# design.net
KiCad netlist of a schematic drawn in EasyEDA Pro
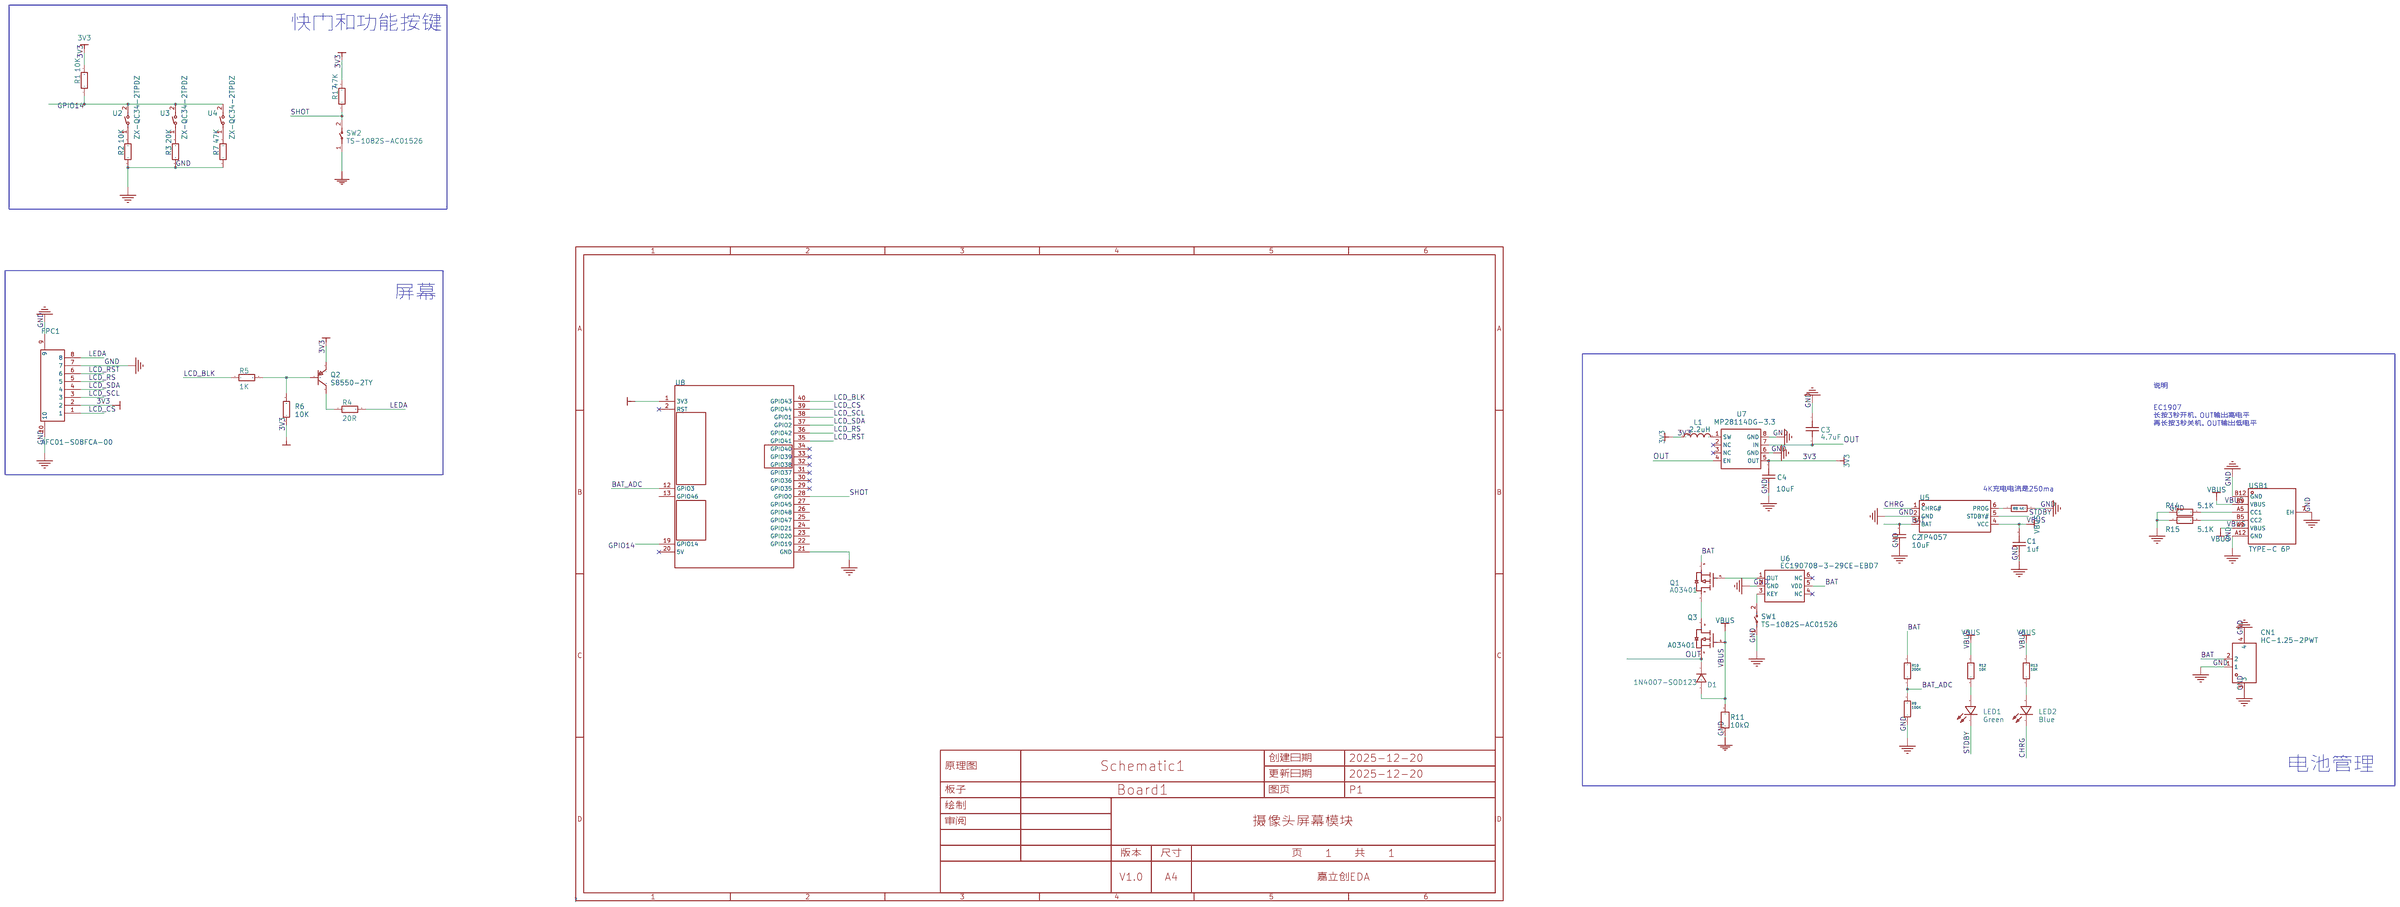
[diagram p0: schematic sheet]

(export (version "E")
  (design (tool "Eeschema 10.0.6"))
  (components
    (comp (ref "C1")
      (value "1uf")
      (footprint "easyedapro:C0603")
      (libsource (lib "easyedapro") (part "Capacitance"))
    )
    (comp (ref "C2")
      (value "10uF")
      (footprint "easyedapro:C0402")
      (description "容值:10uF;精度:±20%;额定电压:6.3V;温度系数:X5R;")
      (fields
        (field (name "Manufacturer Part") "CL05A106MQ5NUNC")
        (field (name "Manufacturer") "SAMSUNG(三星)")
      )
      (libsource (lib "easyedapro") (part "CL05A106MQ5NUNC"))
    )
    (comp (ref "C3")
      (value "4.7uF")
      (footprint "easyedapro:C0603_1")
      (fields
        (field (name "Manufacturer Part") "1uF")
        (field (name "Manufacturer") "SAMSUNG(三星)")
        (field (name "Contributor") "LCSC")
      )
      (libsource (lib "easyedapro") (part "4.7uF"))
    )
    (comp (ref "C4")
      (value "10uF")
      (footprint "easyedapro:C0603_1")
      (fields (field (name "Manufacturer") "SAMSUNG(三星)") (field (name "Contributor") "LCSC"))
      (libsource (lib "easyedapro") (part "10uF"))
    )
    (comp (ref "CN1")
      (value "HC-1.25-2PWT")
      (footprint "easyedapro:CONN-SMD_2P-P1.25-HC-1.25-2PWT")
      (fields (field (name "Manufacturer") "HCTL(华灿天禄)"))
      (libsource (lib "easyedapro") (part "HC-1.25-2PWT"))
    )
    (comp (ref "D1")
      (value "1N4007-SOD123")
      (footprint "easyedapro:SOD-123FL_L2.8-W1.8-LS3.7-RD-1")
      (fields (field (name "Contributor") "LCSC"))
      (libsource (lib "easyedapro") (part "1N4007-SOD123"))
    )
    (comp (ref "FPC1")
      (value "AFC01-S08FCA-00")
      (footprint "easyedapro:FPC-SMD_P0.50-8P_FGS-XJ-H2.0")
      (description "锁定特性:翻盖式;触点类型:下接;触点数量:8P;间距:0.5mm;安装方式:卧贴;")
      (fields (field (name "Manufacturer") "JS(钜硕电子)"))
      (libsource (lib "easyedapro") (part "AFC01-S08FCA-00"))
    )
    (comp (ref "L1")
      (value "2.2uH")
      (footprint "easyedapro:IND-SMD_L4.4-W4.0_PHC0420")
      (fields
        (field (name "Manufacturer Part") "APH0420T2R2M")
        (field (name "Manufacturer") "APV(爱普微)")
        (field (name "Contributor") "lcsc")
      )
      (libsource (lib "easyedapro") (part "2.2uH"))
    )
    (comp (ref "LED1")
      (value "Green")
      (footprint "easyedapro:LED0603-RD")
      (fields (field (name "Manufacturer") "国星光电"))
      (libsource (lib "easyedapro") (part "FC-1608YXK-585F08"))
    )
    (comp (ref "LED2")
      (value "Blue")
      (footprint "easyedapro:LED0603-RD")
      (fields (field (name "Manufacturer") "国星光电"))
      (libsource (lib "easyedapro") (part "FC-1608YXK-585F08"))
    )
    (comp (ref "Q1")
      (value "A03401")
      (footprint "easyedapro:A03401")
      (fields (field (name "Contributor") "shanggan"))
      (libsource (lib "easyedapro") (part "A03401"))
    )
    (comp (ref "Q2")
      (value "S8550-2TY")
      (footprint "easyedapro:SOT-23-3_L2.9-W1.3-P0.95-LS2.4-BR")
      (fields (field (name "Manufacturer") "MDD(辰达半导体)"))
      (libsource (lib "easyedapro") (part "S8550-2TY"))
    )
    (comp (ref "Q3")
      (value "A03401")
      (footprint "easyedapro:A03401")
      (fields (field (name "Contributor") "shanggan"))
      (libsource (lib "easyedapro") (part "A03401_1"))
    )
    (comp (ref "R1") (value "10K") (libsource (lib "easyedapro") (part "电阻")))
    (comp (ref "R2") (value "10K") (libsource (lib "easyedapro") (part "电阻")))
    (comp (ref "R3") (value "20K") (libsource (lib "easyedapro") (part "电阻")))
    (comp (ref "R4")
      (value "20R")
      (footprint "easyedapro:R0603")
      (libsource (lib "easyedapro") (part "电阻_1"))
    )
    (comp (ref "R5") (value "1K") (footprint "easyedapro:R0603") (libsource (lib "easyedapro") (part "电阻_1")))
    (comp (ref "R6")
      (value "10K")
      (footprint "easyedapro:R0603")
      (libsource (lib "easyedapro") (part "电阻_1"))
    )
    (comp (ref "R7") (value "47K") (libsource (lib "easyedapro") (part "电阻")))
    (comp (ref "R8") (value "4K") (footprint "easyedapro:R0603") (libsource (lib "easyedapro") (part "电阻_1")))
    (comp (ref "R9")
      (value "100K")
      (footprint "easyedapro:R0603")
      (libsource (lib "easyedapro") (part "电阻_1"))
    )
    (comp (ref "R10")
      (value "200K")
      (footprint "easyedapro:R0603")
      (libsource (lib "easyedapro") (part "电阻_1"))
    )
    (comp (ref "R11")
      (value "10kΩ")
      (footprint "easyedapro:R0603_1")
      (fields
        (field (name "Manufacturer Part") "APC0603T10K0Z")
        (field (name "Manufacturer") "Ohmite")
        (field (name "Contributor") "lcsc")
      )
      (libsource (lib "easyedapro") (part "10kΩ"))
    )
    (comp (ref "R12")
      (value "10K")
      (footprint "easyedapro:R0603")
      (libsource (lib "easyedapro") (part "电阻_1"))
    )
    (comp (ref "R13")
      (value "10K")
      (footprint "easyedapro:R0603")
      (libsource (lib "easyedapro") (part "电阻_1"))
    )
    (comp (ref "R14")
      (value "5.1K")
      (footprint "easyedapro:R0603")
      (libsource (lib "easyedapro") (part "电阻_1"))
    )
    (comp (ref "R15")
      (value "5.1K")
      (footprint "easyedapro:R0603")
      (libsource (lib "easyedapro") (part "电阻_1"))
    )
    (comp (ref "R17") (value "47K") (libsource (lib "easyedapro") (part "电阻")))
    (comp (ref "SW1")
      (value "TS-1082S-AC01526")
      (footprint "easyedapro:SW-SMD_L3.9-W3.6-LS4.8-EH")
      (fields (field (name "Manufacturer") "XUNPU(讯普)"))
      (libsource (lib "easyedapro") (part "TS-1082S-AC01526"))
    )
    (comp (ref "SW2")
      (value "TS-1082S-AC01526")
      (footprint "easyedapro:SW-SMD_L3.9-W3.6-LS4.8-EH")
      (fields (field (name "Manufacturer") "XUNPU(讯普)"))
      (libsource (lib "easyedapro") (part "TS-1082S-AC01526"))
    )
    (comp (ref "U2")
      (value "ZX-QC34-2TPDZ")
      (footprint "easyedapro:KEY-SMD_L3.9-W3.0-LS5.0-EH")
      (fields (field (name "Manufacturer") "Megastar(兆星)"))
      (libsource (lib "easyedapro") (part "ZX-QC34-2TPDZ"))
    )
    (comp (ref "U3")
      (value "ZX-QC34-2TPDZ")
      (footprint "easyedapro:KEY-SMD_L3.9-W3.0-LS5.0-EH")
      (fields (field (name "Manufacturer") "Megastar(兆星)"))
      (libsource (lib "easyedapro") (part "ZX-QC34-2TPDZ"))
    )
    (comp (ref "U4")
      (value "ZX-QC34-2TPDZ")
      (footprint "easyedapro:KEY-SMD_L3.9-W3.0-LS5.0-EH")
      (fields (field (name "Manufacturer") "Megastar(兆星)"))
      (libsource (lib "easyedapro") (part "ZX-QC34-2TPDZ"))
    )
    (comp (ref "U5")
      (value "TP4057")
      (footprint "easyedapro:SOT-23-6_L2.9-W1.6-P0.95-LS2.8-BR")
      (description "工作电压:4V~6.5V;最大充电电流:500mA;电池类型:锂离子;电池节数:1;")
      (fields (field (name "Manufacturer") "UMW(友台半导体)"))
      (libsource (lib "easyedapro") (part "TP4057_C725791"))
    )
    (comp (ref "U6")
      (value "EC190708-3-29CE-EBD7")
      (footprint "easyedapro:SOT-23-6_L2.9-W1.6-P0.95-LS2.9-BL")
      (fields (field (name "Contributor") "lcsc"))
      (libsource (lib "easyedapro") (part "EC190708-3-29CE-EBD7"))
    )
    (comp (ref "U7")
      (value "MP28114DG-3.3")
      (footprint "easyedapro:MP28114DG-3.3")
      (fields (field (name "Contributor") "httppp"))
      (libsource (lib "easyedapro") (part "MP28114DG-3.3"))
    )
    (comp (ref "U8")
      (value "~")
      (footprint "easyedapro:esp32s3_cam模块")
      (libsource (lib "easyedapro") (part "esp32s3_cam模块"))
    )
    (comp (ref "USB1")
      (value "TYPE-C 6P")
      (footprint "easyedapro:TYPE-C-SMD_TYPE-C-6P")
      (description "连接器类型:Type-C;标准:USB 3.1;公母:母;安装方式:卧贴;触点数量:6P;端口数量:1;额定电流 - 电源:5A;工作温度范围:-40℃~+85℃;")
      (fields (field (name "Manufacturer") "SHOU HAN(首韩)"))
      (libsource (lib "easyedapro") (part "TYPE-C 6P"))
    )
  )
  (nets
    (net (code "1") (name "/BAT") (class "Default")
      (node (ref "C2") (pin "2") (pinfunction "2_2") (pintype "input"))
      (node (ref "CN1") (pin "2") (pinfunction "2_2") (pintype "unspecified"))
      (node (ref "Q1") (pin "2") (pinfunction "S_2") (pintype "unspecified"))
      (node (ref "R10") (pin "2") (pinfunction "2_2") (pintype "input"))
      (node (ref "U5") (pin "3") (pinfunction "BAT_3") (pintype "unspecified"))
      (node (ref "U6") (pin "5") (pinfunction "VDD_5") (pintype "unspecified"))
    )
    (net (code "2") (name "/BAT_ADC") (class "Default")
      (node (ref "R10") (pin "1") (pinfunction "1_1") (pintype "input"))
      (node (ref "R9") (pin "2") (pinfunction "2_2") (pintype "input"))
      (node (ref "U8") (pin "12") (pinfunction "GPIO3_12") (pintype "unspecified"))
    )
    (net (code "3") (name "/CHRG") (class "Default")
      (node (ref "LED2") (pin "1") (pinfunction "K_1") (pintype "unspecified"))
      (node (ref "U5") (pin "1") (pinfunction "CHRG#_1") (pintype "unspecified"))
    )
    (net (code "4") (name "/GPIO14") (class "Default")
      (node (ref "R1") (pin "1") (pinfunction "1_1") (pintype "input"))
      (node (ref "U2") (pin "2") (pinfunction "2_2") (pintype "unspecified"))
      (node (ref "U3") (pin "2") (pinfunction "2_2") (pintype "unspecified"))
      (node (ref "U4") (pin "2") (pinfunction "2_2") (pintype "unspecified"))
      (node (ref "U8") (pin "19") (pinfunction "GPIO14_19") (pintype "unspecified"))
    )
    (net (code "5") (name "/LCD_BLK") (class "Default")
      (node (ref "R5") (pin "1") (pinfunction "1_1") (pintype "input"))
      (node (ref "U8") (pin "40") (pinfunction "GPIO43_40") (pintype "unspecified"))
    )
    (net (code "6") (name "/LCD_CS") (class "Default")
      (node (ref "FPC1") (pin "1") (pinfunction "1_1") (pintype "unspecified"))
      (node (ref "U8") (pin "39") (pinfunction "GPIO44_39") (pintype "unspecified"))
    )
    (net (code "7") (name "/LCD_RS") (class "Default")
      (node (ref "FPC1") (pin "5") (pinfunction "5_5") (pintype "unspecified"))
      (node (ref "U8") (pin "36") (pinfunction "GPIO42_36") (pintype "unspecified"))
    )
    (net (code "8") (name "/LCD_RST") (class "Default")
      (node (ref "FPC1") (pin "6") (pinfunction "6_6") (pintype "unspecified"))
      (node (ref "U8") (pin "35") (pinfunction "GPIO41_35") (pintype "unspecified"))
    )
    (net (code "9") (name "/LCD_SCL") (class "Default")
      (node (ref "FPC1") (pin "3") (pinfunction "3_3") (pintype "unspecified"))
      (node (ref "U8") (pin "38") (pinfunction "GPIO1_38") (pintype "unspecified"))
    )
    (net (code "10") (name "/LCD_SDA") (class "Default")
      (node (ref "FPC1") (pin "4") (pinfunction "4_4") (pintype "unspecified"))
      (node (ref "U8") (pin "37") (pinfunction "GPIO2_37") (pintype "unspecified"))
    )
    (net (code "11") (name "/LEDA") (class "Default")
      (node (ref "FPC1") (pin "8") (pinfunction "8_8") (pintype "unspecified"))
      (node (ref "R4") (pin "2") (pinfunction "2_2") (pintype "input"))
    )
    (net (code "12") (name "/OUT") (class "Default")
      (node (ref "C3") (pin "2") (pinfunction "2_2") (pintype "unspecified"))
      (node (ref "D1") (pin "1") (pinfunction "1_1") (pintype "unspecified"))
      (node (ref "Q3") (pin "2") (pinfunction "S_2") (pintype "unspecified"))
      (node (ref "U7") (pin "4") (pinfunction "EN_4") (pintype "unspecified"))
      (node (ref "U7") (pin "7") (pinfunction "IN_7") (pintype "unspecified"))
    )
    (net (code "13") (name "/SHOT") (class "Default")
      (node (ref "R17") (pin "1") (pinfunction "1_1") (pintype "input"))
      (node (ref "SW2") (pin "2") (pinfunction "2_2") (pintype "unspecified"))
      (node (ref "U8") (pin "28") (pinfunction "GPIO0_28") (pintype "unspecified"))
    )
    (net (code "14") (name "/STDBY") (class "Default")
      (node (ref "LED1") (pin "1") (pinfunction "K_1") (pintype "unspecified"))
      (node (ref "U5") (pin "5") (pinfunction "STDBY#_5") (pintype "unspecified"))
    )
    (net (code "15") (name "3V3") (class "Default")
      (node (ref "C4") (pin "1") (pinfunction "1_1") (pintype "unspecified"))
      (node (ref "FPC1") (pin "2") (pinfunction "2_2") (pintype "unspecified"))
      (node (ref "L1") (pin "1") (pinfunction "1_1") (pintype "unspecified"))
      (node (ref "Q2") (pin "2") (pinfunction "E_2") (pintype "unspecified"))
      (node (ref "R1") (pin "2") (pinfunction "2_2") (pintype "input"))
      (node (ref "R17") (pin "2") (pinfunction "2_2") (pintype "input"))
      (node (ref "R6") (pin "1") (pinfunction "1_1") (pintype "input"))
      (node (ref "U7") (pin "5") (pinfunction "OUT_5") (pintype "unspecified"))
      (node (ref "U8") (pin "1") (pinfunction "3V3_1") (pintype "unspecified"))
    )
    (net (code "16") (name "GND") (class "Default")
      (node (ref "C1") (pin "1") (pinfunction "1_1") (pintype "input"))
      (node (ref "C2") (pin "1") (pinfunction "1_1") (pintype "input"))
      (node (ref "C3") (pin "1") (pinfunction "1_1") (pintype "unspecified"))
      (node (ref "C4") (pin "2") (pinfunction "2_2") (pintype "unspecified"))
      (node (ref "CN1") (pin "1") (pinfunction "1_1") (pintype "unspecified"))
      (node (ref "CN1") (pin "3") (pinfunction "3_3") (pintype "unspecified"))
      (node (ref "CN1") (pin "4") (pinfunction "4_4") (pintype "unspecified"))
      (node (ref "FPC1") (pin "10") (pinfunction "10_10") (pintype "unspecified"))
      (node (ref "FPC1") (pin "7") (pinfunction "7_7") (pintype "unspecified"))
      (node (ref "FPC1") (pin "9") (pinfunction "9_9") (pintype "unspecified"))
      (node (ref "R11") (pin "1") (pinfunction "1_1") (pintype "unspecified"))
      (node (ref "R14") (pin "1") (pinfunction "1_1") (pintype "input"))
      (node (ref "R15") (pin "1") (pinfunction "1_1") (pintype "input"))
      (node (ref "R2") (pin "1") (pinfunction "1_1") (pintype "input"))
      (node (ref "R3") (pin "1") (pinfunction "1_1") (pintype "input"))
      (node (ref "R7") (pin "1") (pinfunction "1_1") (pintype "input"))
      (node (ref "R8") (pin "2") (pinfunction "2_2") (pintype "input"))
      (node (ref "R9") (pin "1") (pinfunction "1_1") (pintype "input"))
      (node (ref "SW1") (pin "1") (pinfunction "1_1") (pintype "unspecified"))
      (node (ref "SW2") (pin "1") (pinfunction "1_1") (pintype "unspecified"))
      (node (ref "U5") (pin "2") (pinfunction "GND_2") (pintype "unspecified"))
      (node (ref "U6") (pin "2") (pinfunction "GND_2") (pintype "unspecified"))
      (node (ref "U7") (pin "6") (pinfunction "GND_6") (pintype "unspecified"))
      (node (ref "U7") (pin "8") (pinfunction "GND_8") (pintype "unspecified"))
      (node (ref "U8") (pin "21") (pinfunction "GND_21") (pintype "unspecified"))
      (node (ref "USB1") (pin "7") (pinfunction "EH_7") (pintype "unspecified"))
      (node (ref "USB1") (pin "A12") (pinfunction "GND_A12") (pintype "unspecified"))
      (node (ref "USB1") (pin "B12") (pinfunction "GND_B12") (pintype "unspecified"))
    )
    (net (code "17") (name "Net-(LED1-A)") (class "Default")
      (node (ref "LED1") (pin "2") (pinfunction "A_2") (pintype "unspecified"))
      (node (ref "R12") (pin "2") (pinfunction "2_2") (pintype "input"))
    )
    (net (code "18") (name "Net-(LED2-A)") (class "Default")
      (node (ref "LED2") (pin "2") (pinfunction "A_2") (pintype "unspecified"))
      (node (ref "R13") (pin "1") (pinfunction "1_1") (pintype "input"))
    )
    (net (code "19") (name "Net-(Q1-D)") (class "Default")
      (node (ref "Q1") (pin "3") (pinfunction "D_3") (pintype "unspecified"))
      (node (ref "Q3") (pin "3") (pinfunction "D_3") (pintype "unspecified"))
    )
    (net (code "20") (name "Net-(Q1-G)") (class "Default")
      (node (ref "Q1") (pin "1") (pinfunction "G_1") (pintype "unspecified"))
      (node (ref "U6") (pin "1") (pinfunction "OUT_1") (pintype "unspecified"))
    )
    (net (code "21") (name "Net-(Q2-B)") (class "Default")
      (node (ref "Q2") (pin "1") (pinfunction "B_1") (pintype "unspecified"))
      (node (ref "R5") (pin "2") (pinfunction "2_2") (pintype "input"))
      (node (ref "R6") (pin "2") (pinfunction "2_2") (pintype "input"))
    )
    (net (code "22") (name "Net-(Q2-C)") (class "Default")
      (node (ref "Q2") (pin "3") (pinfunction "C_3") (pintype "unspecified"))
      (node (ref "R4") (pin "1") (pinfunction "1_1") (pintype "input"))
    )
    (net (code "23") (name "Net-(R2-Pad2)") (class "Default")
      (node (ref "R2") (pin "2") (pinfunction "2_2") (pintype "input"))
      (node (ref "U2") (pin "1") (pinfunction "1_1") (pintype "unspecified"))
    )
    (net (code "24") (name "Net-(R3-Pad2)") (class "Default")
      (node (ref "R3") (pin "2") (pinfunction "2_2") (pintype "input"))
      (node (ref "U3") (pin "1") (pinfunction "1_1") (pintype "unspecified"))
    )
    (net (code "25") (name "Net-(R7-Pad2)") (class "Default")
      (node (ref "R7") (pin "2") (pinfunction "2_2") (pintype "input"))
      (node (ref "U4") (pin "1") (pinfunction "1_1") (pintype "unspecified"))
    )
    (net (code "26") (name "Net-(U5-PROG)") (class "Default")
      (node (ref "R8") (pin "1") (pinfunction "1_1") (pintype "input"))
      (node (ref "U5") (pin "6") (pinfunction "PROG_6") (pintype "unspecified"))
    )
    (net (code "27") (name "Net-(U6-KEY)") (class "Default")
      (node (ref "SW1") (pin "2") (pinfunction "2_2") (pintype "unspecified"))
      (node (ref "U6") (pin "3") (pinfunction "KEY_3") (pintype "unspecified"))
    )
    (net (code "28") (name "Net-(U7-SW)") (class "Default")
      (node (ref "L1") (pin "2") (pinfunction "2_2") (pintype "unspecified"))
      (node (ref "U7") (pin "1") (pinfunction "SW_1") (pintype "unspecified"))
    )
    (net (code "29") (name "Net-(USB1-CC1)") (class "Default")
      (node (ref "R14") (pin "2") (pinfunction "2_2") (pintype "input"))
      (node (ref "USB1") (pin "A5") (pinfunction "CC1_A5") (pintype "unspecified"))
    )
    (net (code "30") (name "Net-(USB1-CC2)") (class "Default")
      (node (ref "R15") (pin "2") (pinfunction "2_2") (pintype "input"))
      (node (ref "USB1") (pin "B5") (pinfunction "CC2_B5") (pintype "unspecified"))
    )
    (net (code "31") (name "VBUS") (class "Default")
      (node (ref "C1") (pin "2") (pinfunction "2_2") (pintype "input"))
      (node (ref "D1") (pin "2") (pinfunction "2_2") (pintype "unspecified"))
      (node (ref "Q3") (pin "1") (pinfunction "G_1") (pintype "unspecified"))
      (node (ref "R11") (pin "2") (pinfunction "2_2") (pintype "unspecified"))
      (node (ref "R12") (pin "1") (pinfunction "1_1") (pintype "input"))
      (node (ref "R13") (pin "2") (pinfunction "2_2") (pintype "input"))
      (node (ref "U5") (pin "4") (pinfunction "VCC_4") (pintype "unspecified"))
      (node (ref "USB1") (pin "A9") (pinfunction "VBUS_A9") (pintype "unspecified"))
      (node (ref "USB1") (pin "B9") (pinfunction "VBUS_B9") (pintype "unspecified"))
    )
    (net (code "32") (name "unconnected-(U6-NC-Pad4)") (class "Default")
      (node (ref "U6") (pin "4") (pinfunction "NC_4") (pintype "unspecified+no_connect"))
    )
    (net (code "33") (name "unconnected-(U6-NC-Pad6)") (class "Default")
      (node (ref "U6") (pin "6") (pinfunction "NC_6") (pintype "unspecified+no_connect"))
    )
    (net (code "34") (name "unconnected-(U7-NC-Pad2)") (class "Default")
      (node (ref "U7") (pin "2") (pinfunction "NC_2") (pintype "unspecified+no_connect"))
    )
    (net (code "35") (name "unconnected-(U7-NC-Pad3)") (class "Default")
      (node (ref "U7") (pin "3") (pinfunction "NC_3") (pintype "unspecified+no_connect"))
    )
    (net (code "36") (name "unconnected-(U8-5V-Pad20)") (class "Default")
      (node (ref "U8") (pin "20") (pinfunction "5V_20") (pintype "unspecified+no_connect"))
    )
    (net (code "37") (name "unconnected-(U8-GPIO19-Pad22)") (class "Default")
      (node (ref "U8") (pin "22") (pinfunction "GPIO19_22") (pintype "unspecified"))
    )
    (net (code "38") (name "unconnected-(U8-GPIO20-Pad23)") (class "Default")
      (node (ref "U8") (pin "23") (pinfunction "GPIO20_23") (pintype "unspecified"))
    )
    (net (code "39") (name "unconnected-(U8-GPIO21-Pad24)") (class "Default")
      (node (ref "U8") (pin "24") (pinfunction "GPIO21_24") (pintype "unspecified"))
    )
    (net (code "40") (name "unconnected-(U8-GPIO35-Pad29)") (class "Default")
      (node (ref "U8") (pin "29") (pinfunction "GPIO35_29") (pintype "unspecified+no_connect"))
    )
    (net (code "41") (name "unconnected-(U8-GPIO36-Pad30)") (class "Default")
      (node (ref "U8") (pin "30") (pinfunction "GPIO36_30") (pintype "unspecified+no_connect"))
    )
    (net (code "42") (name "unconnected-(U8-GPIO37-Pad31)") (class "Default")
      (node (ref "U8") (pin "31") (pinfunction "GPIO37_31") (pintype "unspecified+no_connect"))
    )
    (net (code "43") (name "unconnected-(U8-GPIO38-Pad32)") (class "Default")
      (node (ref "U8") (pin "32") (pinfunction "GPIO38_32") (pintype "unspecified+no_connect"))
    )
    (net (code "44") (name "unconnected-(U8-GPIO39-Pad33)") (class "Default")
      (node (ref "U8") (pin "33") (pinfunction "GPIO39_33") (pintype "unspecified+no_connect"))
    )
    (net (code "45") (name "unconnected-(U8-GPIO40-Pad34)") (class "Default")
      (node (ref "U8") (pin "34") (pinfunction "GPIO40_34") (pintype "unspecified+no_connect"))
    )
    (net (code "46") (name "unconnected-(U8-GPIO45-Pad27)") (class "Default")
      (node (ref "U8") (pin "27") (pinfunction "GPIO45_27") (pintype "unspecified"))
    )
    (net (code "47") (name "unconnected-(U8-GPIO46-Pad13)") (class "Default")
      (node (ref "U8") (pin "13") (pinfunction "GPIO46_13") (pintype "unspecified"))
    )
    (net (code "48") (name "unconnected-(U8-GPIO47-Pad25)") (class "Default")
      (node (ref "U8") (pin "25") (pinfunction "GPIO47_25") (pintype "unspecified"))
    )
    (net (code "49") (name "unconnected-(U8-GPIO48-Pad26)") (class "Default")
      (node (ref "U8") (pin "26") (pinfunction "GPIO48_26") (pintype "unspecified"))
    )
    (net (code "50") (name "unconnected-(U8-RST-Pad2)") (class "Default")
      (node (ref "U8") (pin "2") (pinfunction "RST_2") (pintype "unspecified+no_connect"))
    )
  )
)
